# Shield.net
KiCad netlist of a schematic drawn in EAGLE
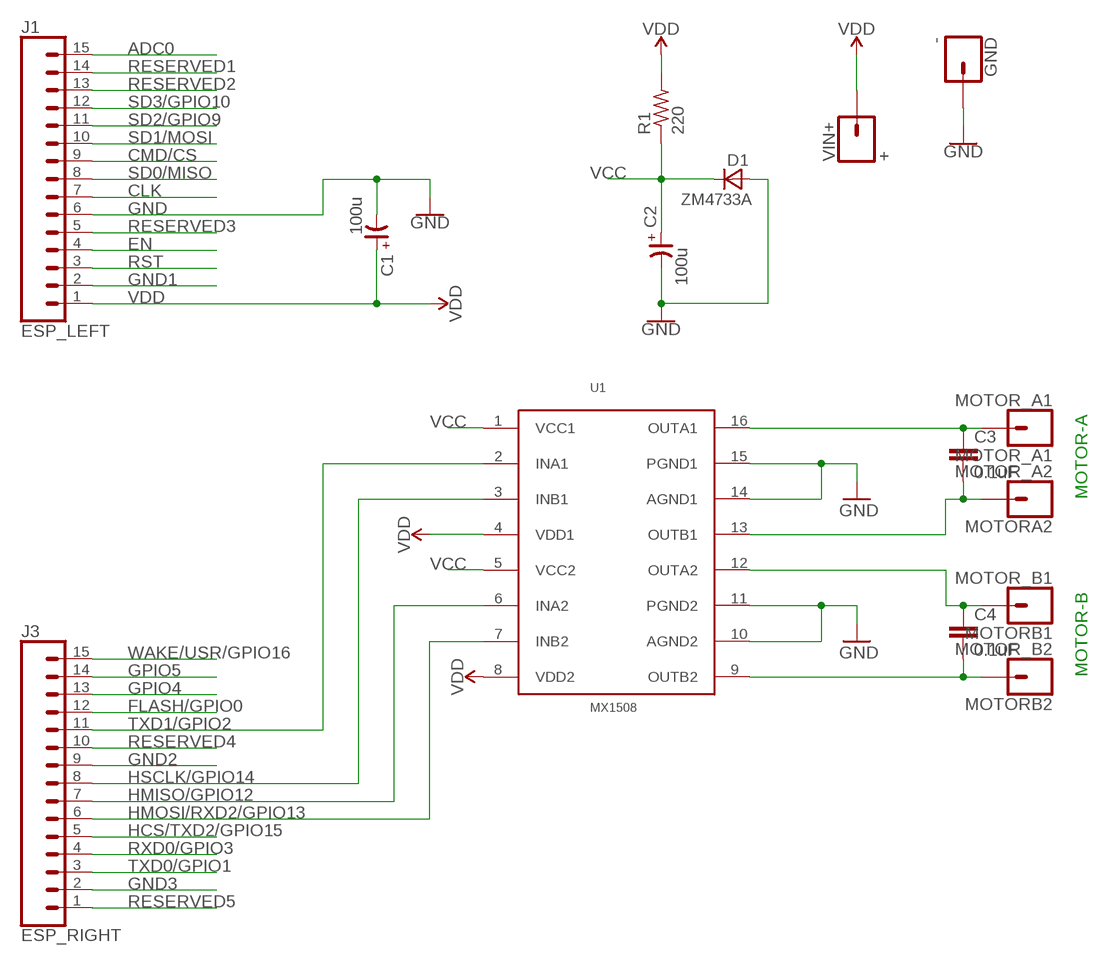
[diagram p0: schematic, sheet 1]

(export (version "E")
  (design (tool "Eeschema 10.0.6"))
  (components
    (comp (ref "C1")
      (value "100u")
      (footprint "eagle-import:SV-D")
      (libsource (lib "eagle-import") (part "CP-SV-D"))
    )
    (comp (ref "C2")
      (value "100u")
      (footprint "eagle-import:SV-D")
      (libsource (lib "eagle-import") (part "CP-SV-D"))
    )
    (comp (ref "C3")
      (value "0.1uF")
      (footprint "eagle-import:CAP-PTH-SMALL-KIT")
      (libsource (lib "eagle-import") (part "0.1UF-KIT-EZ-50V-20%"))
    )
    (comp (ref "C4")
      (value "0.1uF")
      (footprint "eagle-import:CAP-PTH-SMALL-KIT")
      (libsource (lib "eagle-import") (part "0.1UF-KIT-EZ-50V-20%"))
    )
    (comp (ref "D1")
      (value "ZM4733A")
      (footprint "eagle-import:MELF-MLL41")
      (libsource (lib "eagle-import") (part "SM400GENERIC"))
    )
    (comp (ref "GND")
      (value "-")
      (footprint "eagle-import:1X01")
      (libsource (lib "eagle-import") (part "CONN_01"))
    )
    (comp (ref "J1")
      (value "ESP_LEFT")
      (footprint "eagle-import:1X15")
      (libsource (lib "eagle-import") (part "CONN_15"))
    )
    (comp (ref "J3")
      (value "ESP_RIGHT")
      (footprint "eagle-import:1X15")
      (libsource (lib "eagle-import") (part "CONN_15"))
    )
    (comp (ref "MOTORA2")
      (value "MOTOR_A2")
      (footprint "eagle-import:1X01")
      (libsource (lib "eagle-import") (part "CONN_01"))
    )
    (comp (ref "MOTORB1")
      (value "MOTOR_B1")
      (footprint "eagle-import:1X01")
      (libsource (lib "eagle-import") (part "CONN_01"))
    )
    (comp (ref "MOTORB2")
      (value "MOTOR_B2")
      (footprint "eagle-import:1X01")
      (libsource (lib "eagle-import") (part "CONN_01"))
    )
    (comp (ref "MOTOR_A1")
      (value "MOTOR_A1")
      (footprint "eagle-import:1X01")
      (libsource (lib "eagle-import") (part "CONN_01"))
    )
    (comp (ref "R1")
      (value "220")
      (footprint "eagle-import:R2512")
      (libsource (lib "eagle-import") (part "R-US_R2512"))
    )
    (comp (ref "U1")
      (value "MX1508")
      (footprint "eagle-import:MX1508")
      (libsource (lib "eagle-import") (part "MX1508"))
    )
    (comp (ref "VIN+")
      (value "+")
      (footprint "eagle-import:1X01")
      (libsource (lib "eagle-import") (part "CONN_01"))
    )
  )
  (nets
    (net (code "1") (name "/ADC0") (class "Default")
      (node (ref "J1") (pin "15") (pinfunction "15_15") (pintype "passive"))
    )
    (net (code "2") (name "/CLK") (class "Default")
      (node (ref "J1") (pin "7") (pinfunction "7_7") (pintype "passive"))
    )
    (net (code "3") (name "/CMD{slash}CS") (class "Default")
      (node (ref "J1") (pin "9") (pinfunction "9_9") (pintype "passive"))
    )
    (net (code "4") (name "/EN") (class "Default")
      (node (ref "J1") (pin "4") (pinfunction "4_4") (pintype "passive"))
    )
    (net (code "5") (name "/FLASH{slash}GPIO0") (class "Default")
      (node (ref "J3") (pin "12") (pinfunction "12_12") (pintype "passive"))
    )
    (net (code "6") (name "/GND1") (class "Default")
      (node (ref "J1") (pin "2") (pinfunction "2_2") (pintype "passive"))
    )
    (net (code "7") (name "/GND2") (class "Default")
      (node (ref "J3") (pin "9") (pinfunction "9_9") (pintype "passive"))
    )
    (net (code "8") (name "/GND3") (class "Default")
      (node (ref "J3") (pin "2") (pinfunction "2_2") (pintype "passive"))
    )
    (net (code "9") (name "/GPIO4") (class "Default")
      (node (ref "J3") (pin "13") (pinfunction "13_13") (pintype "passive"))
    )
    (net (code "10") (name "/GPIO5") (class "Default")
      (node (ref "J3") (pin "14") (pinfunction "14_14") (pintype "passive"))
    )
    (net (code "11") (name "/HCS{slash}TXD2{slash}GPIO15") (class "Default")
      (node (ref "J3") (pin "5") (pinfunction "5_5") (pintype "passive"))
    )
    (net (code "12") (name "/HMISO{slash}GPIO12") (class "Default")
      (node (ref "J3") (pin "7") (pinfunction "7_7") (pintype "passive"))
      (node (ref "U1") (pin "6") (pinfunction "INA2_6") (pintype "bidirectional"))
    )
    (net (code "13") (name "/HMOSI{slash}RXD2{slash}GPIO13") (class "Default")
      (node (ref "J3") (pin "6") (pinfunction "6_6") (pintype "passive"))
      (node (ref "U1") (pin "7") (pinfunction "INB2_7") (pintype "bidirectional"))
    )
    (net (code "14") (name "/HSCLK{slash}GPIO14") (class "Default")
      (node (ref "J3") (pin "8") (pinfunction "8_8") (pintype "passive"))
      (node (ref "U1") (pin "3") (pinfunction "INB1_3") (pintype "bidirectional"))
    )
    (net (code "15") (name "/RESERVED1") (class "Default")
      (node (ref "J1") (pin "14") (pinfunction "14_14") (pintype "passive"))
    )
    (net (code "16") (name "/RESERVED2") (class "Default")
      (node (ref "J1") (pin "13") (pinfunction "13_13") (pintype "passive"))
    )
    (net (code "17") (name "/RESERVED3") (class "Default")
      (node (ref "J1") (pin "5") (pinfunction "5_5") (pintype "passive"))
    )
    (net (code "18") (name "/RESERVED4") (class "Default")
      (node (ref "J3") (pin "10") (pinfunction "10_10") (pintype "passive"))
    )
    (net (code "19") (name "/RESERVED5") (class "Default")
      (node (ref "J3") (pin "1") (pinfunction "1_1") (pintype "passive"))
    )
    (net (code "20") (name "/RST") (class "Default")
      (node (ref "J1") (pin "3") (pinfunction "3_3") (pintype "passive"))
    )
    (net (code "21") (name "/RXD0{slash}GPIO3") (class "Default")
      (node (ref "J3") (pin "4") (pinfunction "4_4") (pintype "passive"))
    )
    (net (code "22") (name "/SD0{slash}MISO") (class "Default")
      (node (ref "J1") (pin "8") (pinfunction "8_8") (pintype "passive"))
    )
    (net (code "23") (name "/SD1{slash}MOSI") (class "Default")
      (node (ref "J1") (pin "10") (pinfunction "10_10") (pintype "passive"))
    )
    (net (code "24") (name "/SD2{slash}GPIO9") (class "Default")
      (node (ref "J1") (pin "11") (pinfunction "11_11") (pintype "passive"))
    )
    (net (code "25") (name "/SD3{slash}GPIO10") (class "Default")
      (node (ref "J1") (pin "12") (pinfunction "12_12") (pintype "passive"))
    )
    (net (code "26") (name "/TXD0{slash}GPIO1") (class "Default")
      (node (ref "J3") (pin "3") (pinfunction "3_3") (pintype "passive"))
    )
    (net (code "27") (name "/TXD1{slash}GPIO2") (class "Default")
      (node (ref "J3") (pin "11") (pinfunction "11_11") (pintype "passive"))
      (node (ref "U1") (pin "2") (pinfunction "INA1_2") (pintype "bidirectional"))
    )
    (net (code "28") (name "/VCC") (class "Default")
      (node (ref "C2") (pin "+") (pinfunction "+_+") (pintype "passive"))
      (node (ref "D1") (pin "C") (pinfunction "C_C") (pintype "passive"))
      (node (ref "R1") (pin "1") (pinfunction "1_1") (pintype "passive"))
      (node (ref "U1") (pin "1") (pinfunction "VCC1_1") (pintype "power_in"))
      (node (ref "U1") (pin "5") (pinfunction "VCC2_5") (pintype "power_in"))
    )
    (net (code "29") (name "/WAKE{slash}USR{slash}GPIO16") (class "Default")
      (node (ref "J3") (pin "15") (pinfunction "15_15") (pintype "passive"))
    )
    (net (code "30") (name "GND") (class "Default")
      (node (ref "C1") (pin "-") (pinfunction "-_-") (pintype "passive"))
      (node (ref "C2") (pin "-") (pinfunction "-_-") (pintype "passive"))
      (node (ref "D1") (pin "A") (pinfunction "A_A") (pintype "passive"))
      (node (ref "GND") (pin "1") (pinfunction "1_1") (pintype "passive"))
      (node (ref "J1") (pin "6") (pinfunction "6_6") (pintype "passive"))
      (node (ref "U1") (pin "10") (pinfunction "AGND2_10") (pintype "bidirectional"))
      (node (ref "U1") (pin "11") (pinfunction "PGND2_11") (pintype "bidirectional"))
      (node (ref "U1") (pin "14") (pinfunction "AGND1_14") (pintype "bidirectional"))
      (node (ref "U1") (pin "15") (pinfunction "PGND1_15") (pintype "bidirectional"))
    )
    (net (code "31") (name "Net-(U1-OUTA1)") (class "Default")
      (node (ref "C3") (pin "1") (pinfunction "1_1") (pintype "passive"))
      (node (ref "MOTOR_A1") (pin "1") (pinfunction "1_1") (pintype "passive"))
      (node (ref "U1") (pin "16") (pinfunction "OUTA1_16") (pintype "bidirectional"))
    )
    (net (code "32") (name "Net-(U1-OUTA2)") (class "Default")
      (node (ref "C4") (pin "1") (pinfunction "1_1") (pintype "passive"))
      (node (ref "MOTORB1") (pin "1") (pinfunction "1_1") (pintype "passive"))
      (node (ref "U1") (pin "12") (pinfunction "OUTA2_12") (pintype "bidirectional"))
    )
    (net (code "33") (name "Net-(U1-OUTB1)") (class "Default")
      (node (ref "C3") (pin "2") (pinfunction "2_2") (pintype "passive"))
      (node (ref "MOTORA2") (pin "1") (pinfunction "1_1") (pintype "passive"))
      (node (ref "U1") (pin "13") (pinfunction "OUTB1_13") (pintype "bidirectional"))
    )
    (net (code "34") (name "Net-(U1-OUTB2)") (class "Default")
      (node (ref "C4") (pin "2") (pinfunction "2_2") (pintype "passive"))
      (node (ref "MOTORB2") (pin "1") (pinfunction "1_1") (pintype "passive"))
      (node (ref "U1") (pin "9") (pinfunction "OUTB2_9") (pintype "bidirectional"))
    )
    (net (code "35") (name "VDD") (class "Default")
      (node (ref "C1") (pin "+") (pinfunction "+_+") (pintype "passive"))
      (node (ref "J1") (pin "1") (pinfunction "1_1") (pintype "passive"))
      (node (ref "R1") (pin "2") (pinfunction "2_2") (pintype "passive"))
      (node (ref "U1") (pin "4") (pinfunction "VDD1_4") (pintype "power_in"))
      (node (ref "U1") (pin "8") (pinfunction "VDD2_8") (pintype "power_in"))
      (node (ref "VIN+") (pin "1") (pinfunction "1_1") (pintype "passive"))
    )
  )
)
